# IMU.net
KiCad netlist of a schematic drawn in Altium Designer
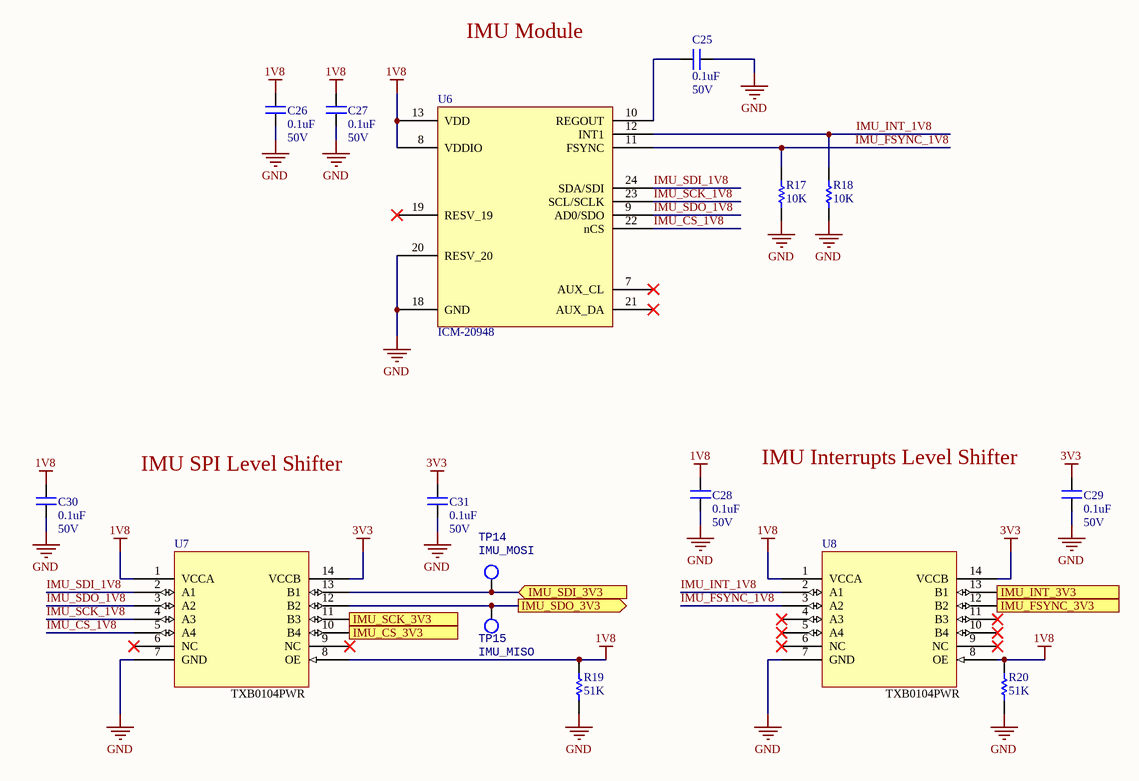
[diagram p0: IMU.SchDoc]

(export (version "E")
  (design (tool "Eeschema 10.0.6"))
  (components
    (comp (ref "C25")
      (value "0.1uF")
      (footprint "CAPC2012X140N")
      (description "CAP CER 0.1UF 50V X7R 0805")
      (fields
        (field (name "TOLERANCE") "10%")
        (field (name "VOLTAGE RATING") "50V")
        (field (name "Comment") "CAP_0.1uF_50V_0805")
      )
      (libsource (lib "UWRT_Schematic_Library_2020") (part "CAP_0.1uF_50V_0805"))
    )
    (comp (ref "C26")
      (value "0.1uF")
      (footprint "CAPC2012X140N")
      (description "CAP CER 0.1UF 50V X7R 0805")
      (fields
        (field (name "TOLERANCE") "10%")
        (field (name "VOLTAGE RATING") "50V")
        (field (name "Comment") "CAP_0.1uF_50V_0805")
      )
      (libsource (lib "UWRT_Schematic_Library_2020") (part "CAP_0.1uF_50V_0805"))
    )
    (comp (ref "C27")
      (value "0.1uF")
      (footprint "CAPC2012X140N")
      (description "CAP CER 0.1UF 50V X7R 0805")
      (fields
        (field (name "TOLERANCE") "10%")
        (field (name "VOLTAGE RATING") "50V")
        (field (name "Comment") "CAP_0.1uF_50V_0805")
      )
      (libsource (lib "UWRT_Schematic_Library_2020") (part "CAP_0.1uF_50V_0805"))
    )
    (comp (ref "C28")
      (value "0.1uF")
      (footprint "CAPC2012X140N")
      (description "CAP CER 0.1UF 50V X7R 0805")
      (fields
        (field (name "TOLERANCE") "10%")
        (field (name "VOLTAGE RATING") "50V")
        (field (name "Comment") "CAP_0.1uF_50V_0805")
      )
      (libsource (lib "UWRT_Schematic_Library_2020") (part "CAP_0.1uF_50V_0805"))
    )
    (comp (ref "C29")
      (value "0.1uF")
      (footprint "CAPC2012X140N")
      (description "CAP CER 0.1UF 50V X7R 0805")
      (fields
        (field (name "TOLERANCE") "10%")
        (field (name "VOLTAGE RATING") "50V")
        (field (name "Comment") "CAP_0.1uF_50V_0805")
      )
      (libsource (lib "UWRT_Schematic_Library_2020") (part "CAP_0.1uF_50V_0805"))
    )
    (comp (ref "C30")
      (value "0.1uF")
      (footprint "CAPC2012X140N")
      (description "CAP CER 0.1UF 50V X7R 0805")
      (fields
        (field (name "TOLERANCE") "10%")
        (field (name "VOLTAGE RATING") "50V")
        (field (name "Comment") "CAP_0.1uF_50V_0805")
      )
      (libsource (lib "UWRT_Schematic_Library_2020") (part "CAP_0.1uF_50V_0805"))
    )
    (comp (ref "C31")
      (value "0.1uF")
      (footprint "CAPC2012X140N")
      (description "CAP CER 0.1UF 50V X7R 0805")
      (fields
        (field (name "TOLERANCE") "10%")
        (field (name "VOLTAGE RATING") "50V")
        (field (name "Comment") "CAP_0.1uF_50V_0805")
      )
      (libsource (lib "UWRT_Schematic_Library_2020") (part "CAP_0.1uF_50V_0805"))
    )
    (comp (ref "R17")
      (value "10K")
      (footprint "RESC0603(1608)_N")
      (description "RES SMD 10K OHM 5% 1/10W 0603")
      (fields (field (name "TOLERANCE") "5%") (field (name "Comment") "RES_10K_0603"))
      (libsource (lib "UWRT_Schematic_Library_2020") (part "RES_10K_0603"))
    )
    (comp (ref "R18")
      (value "10K")
      (footprint "RESC0603(1608)_N")
      (description "RES SMD 10K OHM 5% 1/10W 0603")
      (fields (field (name "TOLERANCE") "5%") (field (name "Comment") "RES_10K_0603"))
      (libsource (lib "UWRT_Schematic_Library_2020") (part "RES_10K_0603"))
    )
    (comp (ref "R19")
      (value "51K")
      (footprint "RESC1608X55N")
      (description "RES SMD 51K OHM 5% 1/10W 0603")
      (fields (field (name "TOLERANCE") "5%") (field (name "Comment") "RES_51K_0603"))
      (libsource (lib "UWRT_Schematic_Library_2020") (part "RES_51K_0603"))
    )
    (comp (ref "R20")
      (value "51K")
      (footprint "RESC1608X55N")
      (description "RES SMD 51K OHM 5% 1/10W 0603")
      (fields (field (name "TOLERANCE") "5%") (field (name "Comment") "RES_51K_0603"))
      (libsource (lib "UWRT_Schematic_Library_2020") (part "RES_51K_0603"))
    )
    (comp (ref "TP14")
      (value "IMU_MOSI")
      (footprint "TESTPOINT_LOOP")
      (description "Loop testpoint through-hole pad")
      (libsource (lib "UWRT_Schematic_Library_2020") (part "TESTPOINT_LOOP"))
    )
    (comp (ref "TP15")
      (value "IMU_MISO")
      (footprint "TESTPOINT_LOOP")
      (description "Loop testpoint through-hole pad")
      (libsource (lib "UWRT_Schematic_Library_2020") (part "TESTPOINT_LOOP"))
    )
    (comp (ref "U6")
      (value "IC_9DOF_IMU")
      (footprint "ICM-20948")
      (description "IMU ACCEL/GYRO/COMPI2C/SPI 24QFN")
      (fields
        (field (name "MANUFACTURER") "TDK InvenSense")
        (field (name "MANUFACTURER PART NUMBER") "ICM-20948")
      )
      (libsource (lib "UWRT_Schematic_Library_2020") (part "IC_9DOF_IMU"))
    )
    (comp (ref "U7")
      (value "TXB0104PWR")
      (footprint "UWRT_Footprint_Library_2020:PW14")
      (fields
        (field (name "GENERIC_PART_NUMBER") "TXB0104")
        (field (name "MANUFACTURER PART NUMBER 1") "TXB0104PWR")
      )
      (libsource (lib "UWRT_Schematic_Library_2020") (part "IC_4CH_LVL_SHIFTER"))
    )
    (comp (ref "U8")
      (value "TXB0104PWR")
      (footprint "UWRT_Footprint_Library_2020:PW14")
      (fields
        (field (name "GENERIC_PART_NUMBER") "TXB0104")
        (field (name "MANUFACTURER PART NUMBER 1") "TXB0104PWR")
      )
      (libsource (lib "UWRT_Schematic_Library_2020") (part "IC_4CH_LVL_SHIFTER"))
    )
  )
  (nets
    (net (code "1") (name "/IMU_CS_1V8") (class "Default")
      (node (ref "U6") (pin "22") (pinfunction "nCS_22") (pintype "passive"))
      (node (ref "U7") (pin "5") (pinfunction "A4_5") (pintype "bidirectional"))
    )
    (net (code "2") (name "/IMU_CS_3V3") (class "Default")
      (node (ref "U7") (pin "10") (pinfunction "B4_10") (pintype "bidirectional"))
    )
    (net (code "3") (name "/IMU_FSYNC_1V8") (class "Default")
      (node (ref "R17") (pin "2") (pinfunction "2_2") (pintype "passive"))
      (node (ref "U6") (pin "11") (pinfunction "FSYNC_11") (pintype "passive"))
      (node (ref "U8") (pin "3") (pinfunction "A2_3") (pintype "bidirectional"))
    )
    (net (code "4") (name "/IMU_FSYNC_3V3") (class "Default")
      (node (ref "U8") (pin "12") (pinfunction "B2_12") (pintype "bidirectional"))
    )
    (net (code "5") (name "/IMU_INT_1V8") (class "Default")
      (node (ref "R18") (pin "2") (pinfunction "2_2") (pintype "passive"))
      (node (ref "U6") (pin "12") (pinfunction "INT1_12") (pintype "passive"))
      (node (ref "U8") (pin "2") (pinfunction "A1_2") (pintype "bidirectional"))
    )
    (net (code "6") (name "/IMU_INT_3V3") (class "Default")
      (node (ref "U8") (pin "13") (pinfunction "B1_13") (pintype "bidirectional"))
    )
    (net (code "7") (name "/IMU_SCK_1V8") (class "Default")
      (node (ref "U6") (pin "23") (pinfunction "SCL/SCLK_23") (pintype "passive"))
      (node (ref "U7") (pin "4") (pinfunction "A3_4") (pintype "bidirectional"))
    )
    (net (code "8") (name "/IMU_SCK_3V3") (class "Default")
      (node (ref "U7") (pin "11") (pinfunction "B3_11") (pintype "bidirectional"))
    )
    (net (code "9") (name "/IMU_SDI_1V8") (class "Default")
      (node (ref "U6") (pin "24") (pinfunction "SDA/SDI_24") (pintype "passive"))
      (node (ref "U7") (pin "2") (pinfunction "A1_2") (pintype "bidirectional"))
    )
    (net (code "10") (name "/IMU_SDI_3V3") (class "Default")
      (node (ref "TP14") (pin "1") (pintype "passive"))
      (node (ref "U7") (pin "13") (pinfunction "B1_13") (pintype "bidirectional"))
    )
    (net (code "11") (name "/IMU_SDO_1V8") (class "Default")
      (node (ref "U6") (pin "9") (pinfunction "AD0/SDO_9") (pintype "passive"))
      (node (ref "U7") (pin "3") (pinfunction "A2_3") (pintype "bidirectional"))
    )
    (net (code "12") (name "/IMU_SDO_3V3") (class "Default")
      (node (ref "TP15") (pin "1") (pintype "passive"))
      (node (ref "U7") (pin "12") (pinfunction "B2_12") (pintype "bidirectional"))
    )
    (net (code "13") (name "1V8") (class "Default")
      (node (ref "C26") (pin "2") (pinfunction "2_2") (pintype "passive"))
      (node (ref "C27") (pin "2") (pinfunction "2_2") (pintype "passive"))
      (node (ref "C28") (pin "2") (pinfunction "2_2") (pintype "passive"))
      (node (ref "C30") (pin "2") (pinfunction "2_2") (pintype "passive"))
      (node (ref "R19") (pin "2") (pinfunction "2_2") (pintype "passive"))
      (node (ref "R20") (pin "2") (pinfunction "2_2") (pintype "passive"))
      (node (ref "U6") (pin "13") (pinfunction "VDD_13") (pintype "passive"))
      (node (ref "U6") (pin "8") (pinfunction "VDDIO_8") (pintype "passive"))
      (node (ref "U7") (pin "1") (pinfunction "VCCA_1") (pintype "power_in"))
      (node (ref "U7") (pin "8") (pinfunction "OE_8") (pintype "input"))
      (node (ref "U8") (pin "1") (pinfunction "VCCA_1") (pintype "power_in"))
      (node (ref "U8") (pin "8") (pinfunction "OE_8") (pintype "input"))
    )
    (net (code "14") (name "3V3") (class "Default")
      (node (ref "C29") (pin "2") (pinfunction "2_2") (pintype "passive"))
      (node (ref "C31") (pin "2") (pinfunction "2_2") (pintype "passive"))
      (node (ref "U7") (pin "14") (pinfunction "VCCB_14") (pintype "power_in"))
      (node (ref "U8") (pin "14") (pinfunction "VCCB_14") (pintype "power_in"))
    )
    (net (code "15") (name "GND") (class "Default")
      (node (ref "C25") (pin "2") (pinfunction "2_2") (pintype "passive"))
      (node (ref "C26") (pin "1") (pinfunction "1_1") (pintype "passive"))
      (node (ref "C27") (pin "1") (pinfunction "1_1") (pintype "passive"))
      (node (ref "C28") (pin "1") (pinfunction "1_1") (pintype "passive"))
      (node (ref "C29") (pin "1") (pinfunction "1_1") (pintype "passive"))
      (node (ref "C30") (pin "1") (pinfunction "1_1") (pintype "passive"))
      (node (ref "C31") (pin "1") (pinfunction "1_1") (pintype "passive"))
      (node (ref "R17") (pin "1") (pinfunction "1_1") (pintype "passive"))
      (node (ref "R18") (pin "1") (pinfunction "1_1") (pintype "passive"))
      (node (ref "R19") (pin "1") (pinfunction "1_1") (pintype "passive"))
      (node (ref "R20") (pin "1") (pinfunction "1_1") (pintype "passive"))
      (node (ref "U6") (pin "18") (pinfunction "GND_18") (pintype "passive"))
      (node (ref "U6") (pin "20") (pinfunction "RESV_20_20") (pintype "passive"))
      (node (ref "U7") (pin "7") (pinfunction "GND_7") (pintype "power_in"))
      (node (ref "U8") (pin "7") (pinfunction "GND_7") (pintype "power_in"))
    )
    (net (code "16") (name "Net-(U6-REGOUT)") (class "Default")
      (node (ref "C25") (pin "1") (pinfunction "1_1") (pintype "passive"))
      (node (ref "U6") (pin "10") (pinfunction "REGOUT_10") (pintype "passive"))
    )
    (net (code "17") (name "unconnected-(U6-AUX_CL-Pad7)") (class "Default")
      (node (ref "U6") (pin "7") (pinfunction "AUX_CL_7") (pintype "passive+no_connect"))
    )
    (net (code "18") (name "unconnected-(U6-AUX_DA-Pad21)") (class "Default")
      (node (ref "U6") (pin "21") (pinfunction "AUX_DA_21") (pintype "passive+no_connect"))
    )
    (net (code "19") (name "unconnected-(U6-RESV_19-Pad19)") (class "Default")
      (node (ref "U6") (pin "19") (pinfunction "RESV_19_19") (pintype "passive+no_connect"))
    )
    (net (code "20") (name "unconnected-(U7-NC-Pad6)") (class "Default")
      (node (ref "U7") (pin "6") (pinfunction "NC_6") (pintype "passive+no_connect"))
    )
    (net (code "21") (name "unconnected-(U7-NC-Pad9)") (class "Default")
      (node (ref "U7") (pin "9") (pinfunction "NC_9") (pintype "passive+no_connect"))
    )
    (net (code "22") (name "unconnected-(U8-A3-Pad4)") (class "Default")
      (node (ref "U8") (pin "4") (pinfunction "A3_4") (pintype "bidirectional+no_connect"))
    )
    (net (code "23") (name "unconnected-(U8-A4-Pad5)") (class "Default")
      (node (ref "U8") (pin "5") (pinfunction "A4_5") (pintype "bidirectional+no_connect"))
    )
    (net (code "24") (name "unconnected-(U8-B3-Pad11)") (class "Default")
      (node (ref "U8") (pin "11") (pinfunction "B3_11") (pintype "bidirectional+no_connect"))
    )
    (net (code "25") (name "unconnected-(U8-B4-Pad10)") (class "Default")
      (node (ref "U8") (pin "10") (pinfunction "B4_10") (pintype "bidirectional+no_connect"))
    )
    (net (code "26") (name "unconnected-(U8-NC-Pad6)") (class "Default")
      (node (ref "U8") (pin "6") (pinfunction "NC_6") (pintype "passive+no_connect"))
    )
    (net (code "27") (name "unconnected-(U8-NC-Pad9)") (class "Default")
      (node (ref "U8") (pin "9") (pinfunction "NC_9") (pintype "passive+no_connect"))
    )
  )
)
